# Sheet1.net
KiCad netlist of a schematic drawn in Altium Designer
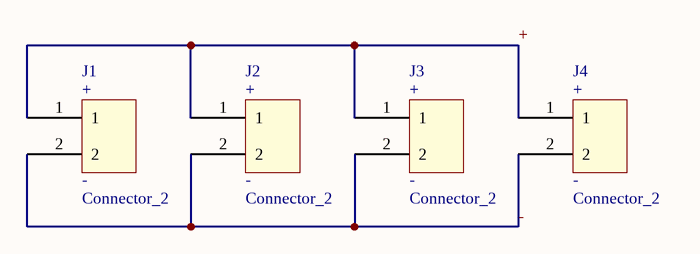
[diagram p0: Sheet1.SchDoc]

(export (version "E")
  (design (tool "Eeschema 10.0.6"))
  (components
    (comp (ref "J1")
      (value "Connector_2")
      (footprint "PCBComponent_1")
      (libsource (lib "XT+PHOENIX") (part "Connector_2"))
    )
    (comp (ref "J2")
      (value "Connector_2")
      (footprint "PCBComponent_1")
      (libsource (lib "XT+PHOENIX") (part "Connector_2"))
    )
    (comp (ref "J3")
      (value "Connector_2")
      (footprint "PCBComponent_1")
      (libsource (lib "XT+PHOENIX") (part "Connector_2"))
    )
    (comp (ref "J4")
      (value "Connector_2")
      (footprint "XT60_FEMALE_PANEL")
      (libsource (lib "XT+PHOENIX") (part "Connector_2"))
    )
  )
  (nets
    (net (code "1") (name "/+") (class "Default")
      (node (ref "J1") (pin "1") (pinfunction "1_1") (pintype "passive"))
      (node (ref "J2") (pin "1") (pinfunction "1_1") (pintype "passive"))
      (node (ref "J3") (pin "1") (pinfunction "1_1") (pintype "passive"))
      (node (ref "J4") (pin "1") (pinfunction "1_1") (pintype "passive"))
    )
    (net (code "2") (name "/-") (class "Default")
      (node (ref "J1") (pin "2") (pinfunction "2_2") (pintype "passive"))
      (node (ref "J2") (pin "2") (pinfunction "2_2") (pintype "passive"))
      (node (ref "J3") (pin "2") (pinfunction "2_2") (pintype "passive"))
      (node (ref "J4") (pin "2") (pinfunction "2_2") (pintype "passive"))
    )
  )
)
